# microSDHC_SDIO.net
KiCad netlist of a schematic drawn in Altium Designer
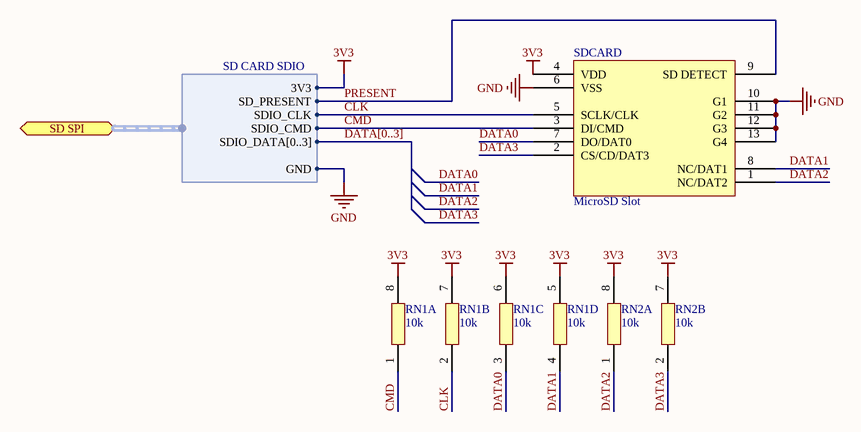
[diagram p0: microSDHC_SDIO.SchDoc]

(export (version "E")
  (design (tool "Eeschema 10.0.6"))
  (components
    (comp (ref "RN1")
      (value "10k")
      (footprint "1206 Resistor Network")
      (libsource (lib "MyLibAltium_v1") (part "1206 Resistor Network"))
    )
    (comp (ref "RN2")
      (value "10k")
      (footprint "1206 Resistor Network")
      (libsource (lib "MyLibAltium_v1") (part "1206 Resistor Network"))
    )
    (comp (ref "SDCARD")
      (value "MicroSD Slot")
      (footprint "MICROSD Slot")
      (libsource (lib "AltiumLib1") (part "MicroSD Slot"))
    )
  )
  (nets
    (net (code "4") (name "/CLK") (class "Default")
      (node (ref "RN1") (pin "2") (pinfunction "2_2") (pintype "passive"))
      (node (ref "SDCARD") (pin "5") (pinfunction "SCLK/CLK_5") (pintype "passive"))
    )
    (net (code "5") (name "/CMD") (class "Default")
      (node (ref "RN1") (pin "1") (pinfunction "1_1") (pintype "passive"))
      (node (ref "SDCARD") (pin "3") (pinfunction "DI/CMD_3") (pintype "passive"))
    )
    (net (code "6") (name "/DATA0") (class "Default")
      (node (ref "RN1") (pin "3") (pinfunction "3_3") (pintype "passive"))
      (node (ref "SDCARD") (pin "7") (pinfunction "DO/DAT0_7") (pintype "passive"))
    )
    (net (code "7") (name "/DATA1") (class "Default")
      (node (ref "RN1") (pin "4") (pinfunction "4_4") (pintype "passive"))
      (node (ref "SDCARD") (pin "8") (pinfunction "NC/DAT1_8") (pintype "passive"))
    )
    (net (code "8") (name "/DATA2") (class "Default")
      (node (ref "RN2") (pin "1") (pinfunction "1_1") (pintype "passive"))
      (node (ref "SDCARD") (pin "1") (pinfunction "NC/DAT2_1") (pintype "passive"))
    )
    (net (code "9") (name "/DATA3") (class "Default")
      (node (ref "RN2") (pin "2") (pinfunction "2_2") (pintype "passive"))
      (node (ref "SDCARD") (pin "2") (pinfunction "CS/CD/DAT3_2") (pintype "passive"))
    )
    (net (code "11") (name "/PRESENT") (class "Default")
      (node (ref "SDCARD") (pin "9") (pinfunction "SD_DETECT_9") (pintype "passive"))
    )
    (net (code "13") (name "3V3") (class "Default")
      (node (ref "RN1") (pin "5") (pinfunction "5_5") (pintype "passive"))
      (node (ref "RN1") (pin "6") (pinfunction "6_6") (pintype "passive"))
      (node (ref "RN1") (pin "7") (pinfunction "7_7") (pintype "passive"))
      (node (ref "RN1") (pin "8") (pinfunction "8_8") (pintype "passive"))
      (node (ref "RN2") (pin "7") (pinfunction "7_7") (pintype "passive"))
      (node (ref "RN2") (pin "8") (pinfunction "8_8") (pintype "passive"))
      (node (ref "SDCARD") (pin "4") (pinfunction "VDD_4") (pintype "passive"))
    )
    (net (code "14") (name "GND") (class "Default")
      (node (ref "SDCARD") (pin "10") (pinfunction "G1_10") (pintype "passive"))
      (node (ref "SDCARD") (pin "11") (pinfunction "G2_11") (pintype "passive"))
      (node (ref "SDCARD") (pin "12") (pinfunction "G3_12") (pintype "passive"))
      (node (ref "SDCARD") (pin "13") (pinfunction "G4_13") (pintype "passive"))
      (node (ref "SDCARD") (pin "6") (pinfunction "VSS_6") (pintype "passive"))
    )
  )
)
